# Sheet2.net
KiCad netlist of a schematic drawn in Altium Designer
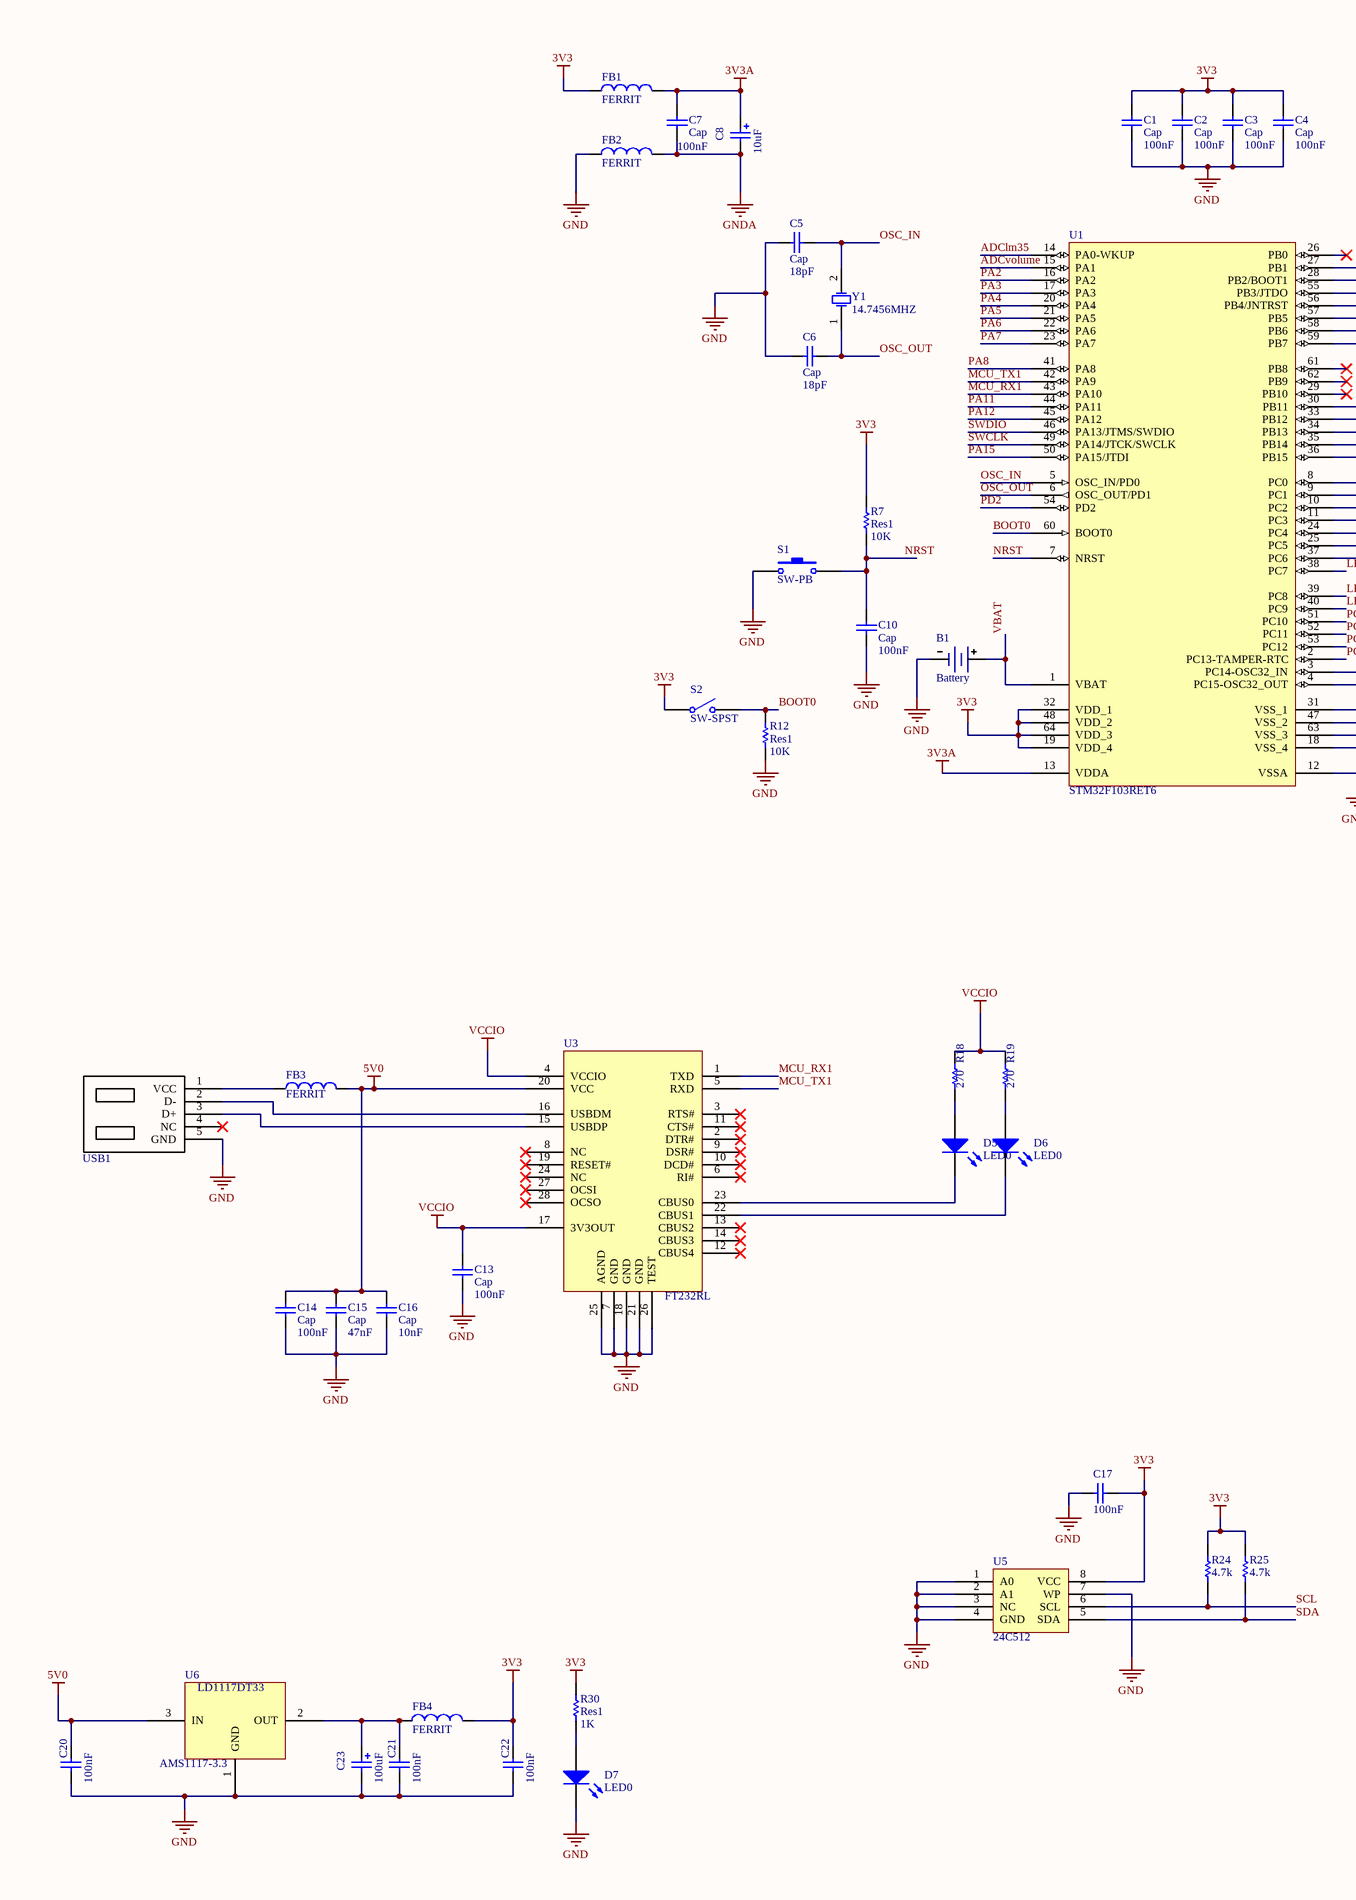
[diagram p0: Sheet2.SchDoc, left]
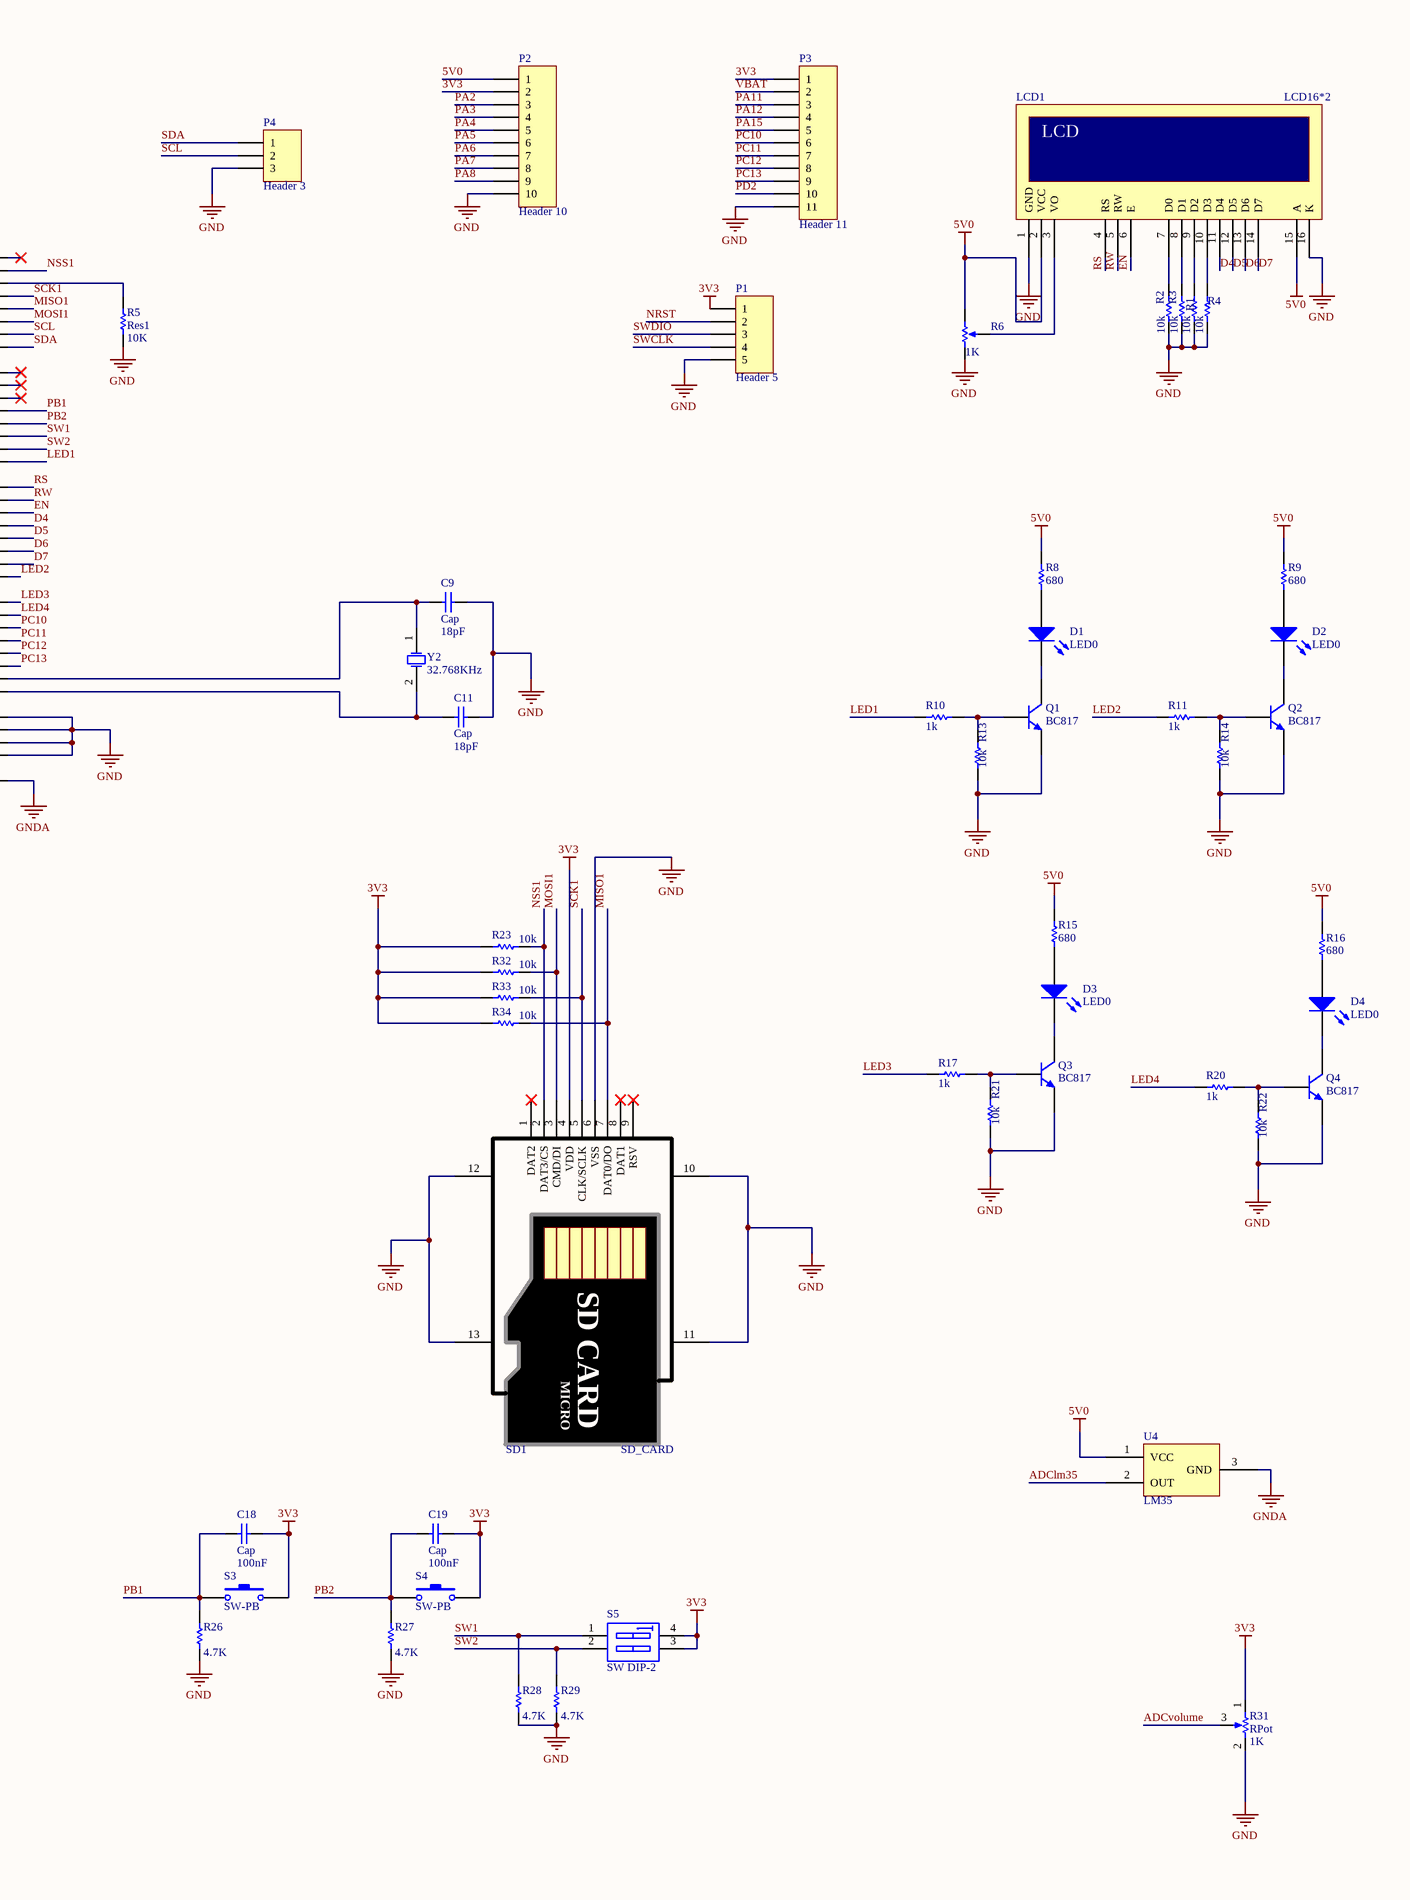
[diagram p1: Sheet2.SchDoc, right]

(export (version "E")
  (design (tool "Eeschema 10.0.6"))
  (components
    (comp (ref "B1")
      (value "Battery")
      (footprint "Battery socket SMD")
      (libsource (lib "ZetaBoard_Lib") (part "Battry Backup"))
    )
    (comp (ref "C1")
      (value "Cap")
      (footprint "SMD_805")
      (description "Capacitor")
      (fields (field (name "ALTIUM_VALUE") "100nF"))
      (libsource (lib "Miscellaneous Devices") (part "Cap"))
    )
    (comp (ref "C2")
      (value "Cap")
      (footprint "SMD_805")
      (description "Capacitor")
      (fields (field (name "ALTIUM_VALUE") "100nF"))
      (libsource (lib "Miscellaneous Devices") (part "Cap"))
    )
    (comp (ref "C3")
      (value "Cap")
      (footprint "SMD_805")
      (description "Capacitor")
      (fields (field (name "ALTIUM_VALUE") "100nF"))
      (libsource (lib "Miscellaneous Devices") (part "Cap"))
    )
    (comp (ref "C4")
      (value "Cap")
      (footprint "SMD_805")
      (description "Capacitor")
      (fields (field (name "ALTIUM_VALUE") "100nF"))
      (libsource (lib "Miscellaneous Devices") (part "Cap"))
    )
    (comp (ref "C5")
      (value "Cap")
      (footprint "SMD_805")
      (description "Capacitor")
      (fields (field (name "ALTIUM_VALUE") "18pF"))
      (libsource (lib "Miscellaneous Devices") (part "Cap"))
    )
    (comp (ref "C6")
      (value "Cap")
      (footprint "SMD_805")
      (description "Capacitor")
      (fields (field (name "ALTIUM_VALUE") "18pF"))
      (libsource (lib "Miscellaneous Devices") (part "Cap"))
    )
    (comp (ref "C7")
      (value "Cap")
      (footprint "SMD_805")
      (description "Capacitor")
      (fields (field (name "ALTIUM_VALUE") "100nF"))
      (libsource (lib "Miscellaneous Devices") (part "Cap"))
    )
    (comp (ref "C8")
      (value "10uF")
      (footprint "C_B")
      (description "Polarized Capacitor (Axial)")
      (fields (field (name "Comment") "Cap Pol2"))
      (libsource (lib "Miscellaneous Devices") (part "Cap Pol2"))
    )
    (comp (ref "C9")
      (value "Cap")
      (footprint "SMD_805")
      (description "Capacitor")
      (fields (field (name "ALTIUM_VALUE") "18pF"))
      (libsource (lib "Miscellaneous Devices") (part "Cap"))
    )
    (comp (ref "C10")
      (value "Cap")
      (footprint "SMD_805")
      (description "Capacitor")
      (fields (field (name "ALTIUM_VALUE") "100nF"))
      (libsource (lib "Miscellaneous Devices") (part "Cap"))
    )
    (comp (ref "C11")
      (value "Cap")
      (footprint "SMD_805")
      (description "Capacitor")
      (fields (field (name "ALTIUM_VALUE") "18pF"))
      (libsource (lib "Miscellaneous Devices") (part "Cap"))
    )
    (comp (ref "C13")
      (value "Cap")
      (footprint "SMD_805")
      (description "Capacitor")
      (fields (field (name "ALTIUM_VALUE") "100nF"))
      (libsource (lib "Miscellaneous Devices") (part "Cap"))
    )
    (comp (ref "C14")
      (value "Cap")
      (footprint "SMD_805")
      (description "Capacitor")
      (fields (field (name "ALTIUM_VALUE") "100nF"))
      (libsource (lib "Miscellaneous Devices") (part "Cap"))
    )
    (comp (ref "C15")
      (value "Cap")
      (footprint "SMD_805")
      (description "Capacitor")
      (fields (field (name "ALTIUM_VALUE") "47nF"))
      (libsource (lib "Miscellaneous Devices") (part "Cap"))
    )
    (comp (ref "C16")
      (value "Cap")
      (footprint "SMD_805")
      (description "Capacitor")
      (fields (field (name "ALTIUM_VALUE") "10nF"))
      (libsource (lib "Miscellaneous Devices") (part "Cap"))
    )
    (comp (ref "C17")
      (value "100nF")
      (footprint "SMD_805")
      (description "Capacitor")
      (fields (field (name "Comment") "Cap"))
      (libsource (lib "Miscellaneous Devices") (part "Cap"))
    )
    (comp (ref "C18")
      (value "Cap")
      (footprint "SMD_805")
      (description "Capacitor")
      (fields (field (name "ALTIUM_VALUE") "100nF"))
      (libsource (lib "Miscellaneous Devices") (part "Cap"))
    )
    (comp (ref "C19")
      (value "Cap")
      (footprint "SMD_805")
      (description "Capacitor")
      (fields (field (name "ALTIUM_VALUE") "100nF"))
      (libsource (lib "Miscellaneous Devices") (part "Cap"))
    )
    (comp (ref "C20")
      (value "100nF")
      (footprint "SMD_805")
      (description "Capacitor")
      (fields (field (name "Comment") "Cap"))
      (libsource (lib "Miscellaneous Devices") (part "Cap"))
    )
    (comp (ref "C21")
      (value "100nF")
      (footprint "SMD_805")
      (description "Capacitor")
      (fields (field (name "Comment") "Cap"))
      (libsource (lib "Miscellaneous Devices") (part "Cap"))
    )
    (comp (ref "C22")
      (value "100nF")
      (footprint "SMD_805")
      (description "Capacitor")
      (fields (field (name "Comment") "Cap"))
      (libsource (lib "Miscellaneous Devices") (part "Cap"))
    )
    (comp (ref "C23")
      (value "100uF")
      (footprint "C_B")
      (description "Polarized Capacitor (Axial)")
      (fields (field (name "Comment") "Cap Pol2"))
      (libsource (lib "Miscellaneous Devices") (part "Cap Pol2"))
    )
    (comp (ref "D1")
      (value "LED0")
      (footprint "SMD_805")
      (description "Typical INFRARED GaAs LED")
      (libsource (lib "Miscellaneous Devices") (part "LED0"))
    )
    (comp (ref "D2")
      (value "LED0")
      (footprint "SMD_805")
      (description "Typical INFRARED GaAs LED")
      (libsource (lib "Miscellaneous Devices") (part "LED0"))
    )
    (comp (ref "D3")
      (value "LED0")
      (footprint "SMD_805")
      (description "Typical INFRARED GaAs LED")
      (libsource (lib "Miscellaneous Devices") (part "LED0"))
    )
    (comp (ref "D4")
      (value "LED0")
      (footprint "SMD_805")
      (description "Typical INFRARED GaAs LED")
      (libsource (lib "Miscellaneous Devices") (part "LED0"))
    )
    (comp (ref "D5")
      (value "LED0")
      (footprint "SMD_805")
      (description "Typical INFRARED GaAs LED")
      (libsource (lib "Miscellaneous Devices") (part "LED0"))
    )
    (comp (ref "D6")
      (value "LED0")
      (footprint "SMD_805")
      (description "Typical INFRARED GaAs LED")
      (libsource (lib "Miscellaneous Devices") (part "LED0"))
    )
    (comp (ref "D7")
      (value "LED0")
      (footprint "SMD_805")
      (description "Typical INFRARED GaAs LED")
      (libsource (lib "Miscellaneous Devices") (part "LED0"))
    )
    (comp (ref "FB1")
      (value "FERRIT")
      (footprint "SMD_805")
      (description "Inductor")
      (libsource (lib "Miscellaneous Devices") (part "Inductor"))
    )
    (comp (ref "FB2")
      (value "FERRIT")
      (footprint "SMD_805")
      (description "Inductor")
      (libsource (lib "Miscellaneous Devices") (part "Inductor"))
    )
    (comp (ref "FB3")
      (value "FERRIT")
      (footprint "SMD_805")
      (description "Inductor")
      (libsource (lib "Miscellaneous Devices") (part "Inductor"))
    )
    (comp (ref "FB4")
      (value "FERRIT")
      (footprint "SMD_805")
      (description "Inductor")
      (libsource (lib "Miscellaneous Devices") (part "Inductor"))
    )
    (comp (ref "LCD1") (value "LCD16*2") (footprint "LCD2X16") (libsource (lib "LCD") (part "LCD16*2")))
    (comp (ref "P1")
      (value "Header 5")
      (footprint "HDR1X5")
      (description "Header, 5-Pin")
      (libsource (lib "Miscellaneous Connectors") (part "Header 5"))
    )
    (comp (ref "P2")
      (value "Header 10")
      (footprint "HDR1X10")
      (description "Header, 10-Pin")
      (libsource (lib "Miscellaneous Connectors") (part "Header 10"))
    )
    (comp (ref "P3")
      (value "Header 11")
      (footprint "HDR1X11")
      (description "Header, 11-Pin")
      (libsource (lib "Miscellaneous Connectors") (part "Header 11"))
    )
    (comp (ref "P4")
      (value "Header 3")
      (footprint "HDR1X3")
      (description "Header, 3-Pin")
      (libsource (lib "Miscellaneous Connectors") (part "Header 3"))
    )
    (comp (ref "Q1")
      (value "BC817")
      (footprint "SOT23")
      (description "NPN General Purpose Amplifier")
      (libsource (lib "Miscellaneous Devices") (part "2N3904"))
    )
    (comp (ref "Q2")
      (value "BC817")
      (footprint "SOT23")
      (description "NPN General Purpose Amplifier")
      (libsource (lib "Miscellaneous Devices") (part "2N3904"))
    )
    (comp (ref "Q3")
      (value "BC817")
      (footprint "SOT23")
      (description "NPN General Purpose Amplifier")
      (libsource (lib "Miscellaneous Devices") (part "2N3904"))
    )
    (comp (ref "Q4")
      (value "BC817")
      (footprint "SOT23")
      (description "NPN General Purpose Amplifier")
      (libsource (lib "Miscellaneous Devices") (part "2N3904"))
    )
    (comp (ref "R1")
      (value "10k")
      (footprint "SMD_805")
      (description "Resistor")
      (fields (field (name "Comment") "Res1"))
      (libsource (lib "Miscellaneous Devices") (part "Res1"))
    )
    (comp (ref "R2")
      (value "10k")
      (footprint "SMD_805")
      (description "Resistor")
      (fields (field (name "Comment") "Res1"))
      (libsource (lib "Miscellaneous Devices") (part "Res1"))
    )
    (comp (ref "R3")
      (value "10k")
      (footprint "SMD_805")
      (description "Resistor")
      (fields (field (name "Comment") "Res1"))
      (libsource (lib "Miscellaneous Devices") (part "Res1"))
    )
    (comp (ref "R4")
      (value "10k")
      (footprint "SMD_805")
      (description "Resistor")
      (fields (field (name "Comment") "Res1"))
      (libsource (lib "Miscellaneous Devices") (part "Res1"))
    )
    (comp (ref "R5")
      (value "Res1")
      (footprint "SMD_805")
      (description "Resistor")
      (fields (field (name "ALTIUM_VALUE") "10K"))
      (libsource (lib "Miscellaneous Devices") (part "Res1"))
    )
    (comp (ref "R6")
      (value "1K")
      (footprint "pot")
      (description "Potentiometer")
      (fields (field (name "Comment") "RPot"))
      (libsource (lib "Miscellaneous Devices") (part "RPot"))
    )
    (comp (ref "R7")
      (value "Res1")
      (footprint "SMD_805")
      (description "Resistor")
      (fields (field (name "ALTIUM_VALUE") "10K"))
      (libsource (lib "Miscellaneous Devices") (part "Res1"))
    )
    (comp (ref "R8")
      (value "680")
      (footprint "SMD_805")
      (description "Resistor")
      (fields (field (name "Comment") "Res1"))
      (libsource (lib "Miscellaneous Devices") (part "Res1"))
    )
    (comp (ref "R9")
      (value "680")
      (footprint "SMD_805")
      (description "Resistor")
      (fields (field (name "Comment") "Res1"))
      (libsource (lib "Miscellaneous Devices") (part "Res1"))
    )
    (comp (ref "R10")
      (value "1k")
      (footprint "SMD_805")
      (description "Resistor")
      (fields (field (name "Comment") "Res1"))
      (libsource (lib "Miscellaneous Devices") (part "Res1"))
    )
    (comp (ref "R11")
      (value "1k")
      (footprint "SMD_805")
      (description "Resistor")
      (fields (field (name "Comment") "Res1"))
      (libsource (lib "Miscellaneous Devices") (part "Res1"))
    )
    (comp (ref "R12")
      (value "Res1")
      (footprint "SMD_805")
      (description "Resistor")
      (fields (field (name "ALTIUM_VALUE") "10K"))
      (libsource (lib "Miscellaneous Devices") (part "Res1"))
    )
    (comp (ref "R13")
      (value "10k")
      (footprint "SMD_805")
      (description "Resistor")
      (fields (field (name "Comment") "Res1"))
      (libsource (lib "Miscellaneous Devices") (part "Res1"))
    )
    (comp (ref "R14")
      (value "10k")
      (footprint "SMD_805")
      (description "Resistor")
      (fields (field (name "Comment") "Res1"))
      (libsource (lib "Miscellaneous Devices") (part "Res1"))
    )
    (comp (ref "R15")
      (value "680")
      (footprint "SMD_805")
      (description "Resistor")
      (fields (field (name "Comment") "Res1"))
      (libsource (lib "Miscellaneous Devices") (part "Res1"))
    )
    (comp (ref "R16")
      (value "680")
      (footprint "SMD_805")
      (description "Resistor")
      (fields (field (name "Comment") "Res1"))
      (libsource (lib "Miscellaneous Devices") (part "Res1"))
    )
    (comp (ref "R17")
      (value "1k")
      (footprint "SMD_805")
      (description "Resistor")
      (fields (field (name "Comment") "Res1"))
      (libsource (lib "Miscellaneous Devices") (part "Res1"))
    )
    (comp (ref "R18")
      (value "270")
      (footprint "SMD_805")
      (description "Resistor")
      (fields (field (name "Comment") "Res1"))
      (libsource (lib "Miscellaneous Devices") (part "Res1"))
    )
    (comp (ref "R19")
      (value "270")
      (footprint "SMD_805")
      (description "Resistor")
      (fields (field (name "Comment") "Res1"))
      (libsource (lib "Miscellaneous Devices") (part "Res1"))
    )
    (comp (ref "R20")
      (value "1k")
      (footprint "SMD_805")
      (description "Resistor")
      (fields (field (name "Comment") "Res1"))
      (libsource (lib "Miscellaneous Devices") (part "Res1"))
    )
    (comp (ref "R21")
      (value "10k")
      (footprint "SMD_805")
      (description "Resistor")
      (fields (field (name "Comment") "Res1"))
      (libsource (lib "Miscellaneous Devices") (part "Res1"))
    )
    (comp (ref "R22")
      (value "10k")
      (footprint "SMD_805")
      (description "Resistor")
      (fields (field (name "Comment") "Res1"))
      (libsource (lib "Miscellaneous Devices") (part "Res1"))
    )
    (comp (ref "R23")
      (value "10k")
      (footprint "SMD_805")
      (description "Resistor")
      (fields (field (name "Comment") "Res1"))
      (libsource (lib "Miscellaneous Devices") (part "Res1"))
    )
    (comp (ref "R24")
      (value "4.7k")
      (footprint "SMD_805")
      (description "Resistor")
      (fields (field (name "Comment") "Res1"))
      (libsource (lib "Miscellaneous Devices") (part "Res1"))
    )
    (comp (ref "R25")
      (value "4.7k")
      (footprint "SMD_805")
      (description "Resistor")
      (fields (field (name "Comment") "Res1"))
      (libsource (lib "Miscellaneous Devices") (part "Res1"))
    )
    (comp (ref "R26")
      (value "4.7K")
      (footprint "SMD_805")
      (description "Resistor")
      (fields (field (name "Comment") "Res1"))
      (libsource (lib "Miscellaneous Devices") (part "Res1"))
    )
    (comp (ref "R27")
      (value "4.7K")
      (footprint "SMD_805")
      (description "Resistor")
      (fields (field (name "Comment") "Res1"))
      (libsource (lib "Miscellaneous Devices") (part "Res1"))
    )
    (comp (ref "R28")
      (value "4.7K")
      (footprint "SMD_805")
      (description "Resistor")
      (fields (field (name "Comment") "Res1"))
      (libsource (lib "Miscellaneous Devices") (part "Res1"))
    )
    (comp (ref "R29")
      (value "4.7K")
      (footprint "SMD_805")
      (description "Resistor")
      (fields (field (name "Comment") "Res1"))
      (libsource (lib "Miscellaneous Devices") (part "Res1"))
    )
    (comp (ref "R30")
      (value "Res1")
      (footprint "SMD_805")
      (description "Resistor")
      (fields (field (name "ALTIUM_VALUE") "1K"))
      (libsource (lib "Miscellaneous Devices") (part "Res1"))
    )
    (comp (ref "R31")
      (value "RPot")
      (footprint "pot")
      (description "Potentiometer")
      (fields (field (name "ALTIUM_VALUE") "1K"))
      (libsource (lib "") (part "RPot_1"))
    )
    (comp (ref "R32")
      (value "10k")
      (footprint "SMD_805")
      (description "Resistor")
      (fields (field (name "Comment") "Res1"))
      (libsource (lib "Miscellaneous Devices") (part "Res1"))
    )
    (comp (ref "R33")
      (value "10k")
      (footprint "SMD_805")
      (description "Resistor")
      (fields (field (name "Comment") "Res1"))
      (libsource (lib "Miscellaneous Devices") (part "Res1"))
    )
    (comp (ref "R34")
      (value "10k")
      (footprint "SMD_805")
      (description "Resistor")
      (fields (field (name "Comment") "Res1"))
      (libsource (lib "Miscellaneous Devices") (part "Res1"))
    )
    (comp (ref "S1")
      (value "SW-PB")
      (footprint "smd_button")
      (description "Switch")
      (libsource (lib "Miscellaneous Devices") (part "SW-PB"))
    )
    (comp (ref "S2")
      (value "SW-SPST")
      (footprint "KEY1")
      (description "Single-Pole, Single-Throw Switch")
      (libsource (lib "Miscellaneous Devices") (part "SW-SPST"))
    )
    (comp (ref "S3")
      (value "SW-PB")
      (footprint "smd_button")
      (description "Switch")
      (libsource (lib "Miscellaneous Devices") (part "SW-PB"))
    )
    (comp (ref "S4")
      (value "SW-PB")
      (footprint "smd_button")
      (description "Switch")
      (libsource (lib "Miscellaneous Devices") (part "SW-PB"))
    )
    (comp (ref "S5")
      (value "SW DIP-2")
      (footprint "DIP-4")
      (description "DIP Switch, 2 Position, SPST")
      (libsource (lib "Miscellaneous Devices") (part "SW DIP-2"))
    )
    (comp (ref "SD1")
      (value "SD_CARD")
      (footprint "Micro SD Card")
      (libsource (lib "MICRO_SD_CARD_HOLDER") (part "MICRO_SD_CARD_HOLDER"))
    )
    (comp (ref "U1")
      (value "STM32F103RET6")
      (footprint "LQFP64")
      (description "STM32 ARM-based 32-bit MCU with 64 Kbytes Flash, 64-pin LQFP, Industrial Temperature")
      (libsource (lib "ST Microcontroller 32-Bit STM32") (part "STM32F103R8T6"))
    )
    (comp (ref "U3") (value "FT232RL") (footprint "SOP28") (libsource (lib "FT232RL") (part "FT232RL")))
    (comp (ref "U4")
      (value "LM35")
      (footprint "LM35-TO92")
      (description "LM35 Temperature Sensor")
      (libsource (lib "altium-import") (part "root_0_LM35_"))
    )
    (comp (ref "U5") (value "24C512") (footprint "SOP8") (libsource (lib "24Cxx") (part "24Cxx")))
    (comp (ref "U6")
      (value "AMS1117-3.3")
      (footprint "SOT223")
      (libsource (lib "LD1117DT33") (part "LD1117DT33"))
    )
    (comp (ref "USB1")
      (value "MICRO_USB")
      (footprint "MINI_USB")
      (libsource (lib "MICRO_USB") (part "MICRO_USB"))
    )
    (comp (ref "Y1")
      (value "14.7456MHZ")
      (footprint "xtal_smd")
      (description "Crystal Oscillator")
      (libsource (lib "Miscellaneous Devices") (part "XTAL"))
    )
    (comp (ref "Y2")
      (value "32.768KHz")
      (footprint "XTAL_RTC")
      (description "Crystal Oscillator")
      (libsource (lib "Miscellaneous Devices") (part "XTAL"))
    )
  )
  (nets
    (net (code "1") (name "/ADClm35") (class "Default")
      (node (ref "U1") (pin "14") (pinfunction "PA0-WKUP_14") (pintype "bidirectional"))
      (node (ref "U4") (pin "2") (pinfunction "OUT_2") (pintype "passive"))
    )
    (net (code "2") (name "/ADCvolume") (class "Default")
      (node (ref "R31") (pin "3") (pinfunction "TAP_3") (pintype "passive"))
      (node (ref "U1") (pin "15") (pinfunction "PA1_15") (pintype "bidirectional"))
    )
    (net (code "3") (name "/BOOT0") (class "Default")
      (node (ref "R12") (pin "2") (pinfunction "2_2") (pintype "passive"))
      (node (ref "S2") (pin "2") (pinfunction "NO_2") (pintype "passive"))
      (node (ref "U1") (pin "60") (pinfunction "BOOT0_60") (pintype "input"))
    )
    (net (code "4") (name "/D4") (class "Default")
      (node (ref "LCD1") (pin "11") (pinfunction "D4_11") (pintype "passive"))
      (node (ref "U1") (pin "11") (pinfunction "PC3_11") (pintype "bidirectional"))
    )
    (net (code "5") (name "/D5") (class "Default")
      (node (ref "LCD1") (pin "12") (pinfunction "D5_12") (pintype "passive"))
      (node (ref "U1") (pin "24") (pinfunction "PC4_24") (pintype "bidirectional"))
    )
    (net (code "6") (name "/D6") (class "Default")
      (node (ref "LCD1") (pin "13") (pinfunction "D6_13") (pintype "passive"))
      (node (ref "U1") (pin "25") (pinfunction "PC5_25") (pintype "bidirectional"))
    )
    (net (code "7") (name "/D7") (class "Default")
      (node (ref "LCD1") (pin "14") (pinfunction "D7_14") (pintype "passive"))
      (node (ref "U1") (pin "37") (pinfunction "PC6_37") (pintype "bidirectional"))
    )
    (net (code "8") (name "/EN") (class "Default")
      (node (ref "LCD1") (pin "6") (pinfunction "E_6") (pintype "passive"))
      (node (ref "U1") (pin "10") (pinfunction "PC2_10") (pintype "bidirectional"))
    )
    (net (code "9") (name "/LED1") (class "Default")
      (node (ref "R10") (pin "1") (pinfunction "1_1") (pintype "passive"))
      (node (ref "U1") (pin "36") (pinfunction "PB15_36") (pintype "bidirectional"))
    )
    (net (code "10") (name "/LED2") (class "Default")
      (node (ref "R11") (pin "1") (pinfunction "1_1") (pintype "passive"))
      (node (ref "U1") (pin "38") (pinfunction "PC7_38") (pintype "bidirectional"))
    )
    (net (code "11") (name "/LED3") (class "Default")
      (node (ref "R17") (pin "1") (pinfunction "1_1") (pintype "passive"))
      (node (ref "U1") (pin "39") (pinfunction "PC8_39") (pintype "bidirectional"))
    )
    (net (code "12") (name "/LED4") (class "Default")
      (node (ref "R20") (pin "1") (pinfunction "1_1") (pintype "passive"))
      (node (ref "U1") (pin "40") (pinfunction "PC9_40") (pintype "bidirectional"))
    )
    (net (code "13") (name "/MCU_RX1") (class "Default")
      (node (ref "U1") (pin "43") (pinfunction "PA10_43") (pintype "bidirectional"))
      (node (ref "U3") (pin "1") (pinfunction "TXD_1") (pintype "passive"))
    )
    (net (code "14") (name "/MCU_TX1") (class "Default")
      (node (ref "U1") (pin "42") (pinfunction "PA9_42") (pintype "bidirectional"))
      (node (ref "U3") (pin "5") (pinfunction "RXD_5") (pintype "passive"))
    )
    (net (code "15") (name "/MISO1") (class "Default")
      (node (ref "R34") (pin "1") (pinfunction "1_1") (pintype "passive"))
      (node (ref "SD1") (pin "7") (pinfunction "DAT0/DO_7") (pintype "passive"))
      (node (ref "U1") (pin "56") (pinfunction "PB4/JNTRST_56") (pintype "bidirectional"))
    )
    (net (code "16") (name "/MOSI1") (class "Default")
      (node (ref "R32") (pin "1") (pinfunction "1_1") (pintype "passive"))
      (node (ref "SD1") (pin "3") (pinfunction "CMD/DI_3") (pintype "passive"))
      (node (ref "U1") (pin "57") (pinfunction "PB5_57") (pintype "bidirectional"))
    )
    (net (code "17") (name "/NRST") (class "Default")
      (node (ref "C10") (pin "2") (pinfunction "2_2") (pintype "passive"))
      (node (ref "P1") (pin "2") (pinfunction "2_2") (pintype "passive"))
      (node (ref "R7") (pin "1") (pinfunction "1_1") (pintype "passive"))
      (node (ref "S1") (pin "2") (pinfunction "2_2") (pintype "passive"))
      (node (ref "U1") (pin "7") (pinfunction "NRST_7") (pintype "bidirectional"))
    )
    (net (code "18") (name "/NSS1") (class "Default")
      (node (ref "R23") (pin "1") (pinfunction "1_1") (pintype "passive"))
      (node (ref "SD1") (pin "2") (pinfunction "DAT3/CS_2") (pintype "passive"))
      (node (ref "U1") (pin "27") (pinfunction "PB1_27") (pintype "bidirectional"))
    )
    (net (code "19") (name "/OSC_IN") (class "Default")
      (node (ref "C5") (pin "2") (pinfunction "2_2") (pintype "passive"))
      (node (ref "U1") (pin "5") (pinfunction "OSC_IN/PD0_5") (pintype "input"))
      (node (ref "Y1") (pin "2") (pinfunction "OSC2_2") (pintype "passive"))
    )
    (net (code "20") (name "/OSC_OUT") (class "Default")
      (node (ref "C6") (pin "2") (pinfunction "2_2") (pintype "passive"))
      (node (ref "U1") (pin "6") (pinfunction "OSC_OUT/PD1_6") (pintype "output"))
      (node (ref "Y1") (pin "1") (pinfunction "OSC1_1") (pintype "passive"))
    )
    (net (code "21") (name "/PA2") (class "Default")
      (node (ref "P2") (pin "3") (pinfunction "3_3") (pintype "passive"))
      (node (ref "U1") (pin "16") (pinfunction "PA2_16") (pintype "bidirectional"))
    )
    (net (code "22") (name "/PA3") (class "Default")
      (node (ref "P2") (pin "4") (pinfunction "4_4") (pintype "passive"))
      (node (ref "U1") (pin "17") (pinfunction "PA3_17") (pintype "bidirectional"))
    )
    (net (code "23") (name "/PA4") (class "Default")
      (node (ref "P2") (pin "5") (pinfunction "5_5") (pintype "passive"))
      (node (ref "U1") (pin "20") (pinfunction "PA4_20") (pintype "bidirectional"))
    )
    (net (code "24") (name "/PA5") (class "Default")
      (node (ref "P2") (pin "6") (pinfunction "6_6") (pintype "passive"))
      (node (ref "U1") (pin "21") (pinfunction "PA5_21") (pintype "bidirectional"))
    )
    (net (code "25") (name "/PA6") (class "Default")
      (node (ref "P2") (pin "7") (pinfunction "7_7") (pintype "passive"))
      (node (ref "U1") (pin "22") (pinfunction "PA6_22") (pintype "bidirectional"))
    )
    (net (code "26") (name "/PA7") (class "Default")
      (node (ref "P2") (pin "8") (pinfunction "8_8") (pintype "passive"))
      (node (ref "U1") (pin "23") (pinfunction "PA7_23") (pintype "bidirectional"))
    )
    (net (code "27") (name "/PA8") (class "Default")
      (node (ref "P2") (pin "9") (pinfunction "9_9") (pintype "passive"))
      (node (ref "U1") (pin "41") (pinfunction "PA8_41") (pintype "bidirectional"))
    )
    (net (code "28") (name "/PA11") (class "Default")
      (node (ref "P3") (pin "3") (pinfunction "3_3") (pintype "passive"))
      (node (ref "U1") (pin "44") (pinfunction "PA11_44") (pintype "bidirectional"))
    )
    (net (code "29") (name "/PA12") (class "Default")
      (node (ref "P3") (pin "4") (pinfunction "4_4") (pintype "passive"))
      (node (ref "U1") (pin "45") (pinfunction "PA12_45") (pintype "bidirectional"))
    )
    (net (code "30") (name "/PA15") (class "Default")
      (node (ref "P3") (pin "5") (pinfunction "5_5") (pintype "passive"))
      (node (ref "U1") (pin "50") (pinfunction "PA15/JTDI_50") (pintype "bidirectional"))
    )
    (net (code "31") (name "/PB1") (class "Default")
      (node (ref "C18") (pin "1") (pinfunction "1_1") (pintype "passive"))
      (node (ref "R26") (pin "2") (pinfunction "2_2") (pintype "passive"))
      (node (ref "S3") (pin "1") (pinfunction "1_1") (pintype "passive"))
      (node (ref "U1") (pin "30") (pinfunction "PB11_30") (pintype "bidirectional"))
    )
    (net (code "32") (name "/PB2") (class "Default")
      (node (ref "C19") (pin "1") (pinfunction "1_1") (pintype "passive"))
      (node (ref "R27") (pin "2") (pinfunction "2_2") (pintype "passive"))
      (node (ref "S4") (pin "1") (pinfunction "1_1") (pintype "passive"))
      (node (ref "U1") (pin "33") (pinfunction "PB12_33") (pintype "bidirectional"))
    )
    (net (code "33") (name "/PC10") (class "Default")
      (node (ref "P3") (pin "6") (pinfunction "6_6") (pintype "passive"))
      (node (ref "U1") (pin "51") (pinfunction "PC10_51") (pintype "bidirectional"))
    )
    (net (code "34") (name "/PC11") (class "Default")
      (node (ref "P3") (pin "7") (pinfunction "7_7") (pintype "passive"))
      (node (ref "U1") (pin "52") (pinfunction "PC11_52") (pintype "bidirectional"))
    )
    (net (code "35") (name "/PC12") (class "Default")
      (node (ref "P3") (pin "8") (pinfunction "8_8") (pintype "passive"))
      (node (ref "U1") (pin "53") (pinfunction "PC12_53") (pintype "bidirectional"))
    )
    (net (code "36") (name "/PC13") (class "Default")
      (node (ref "P3") (pin "9") (pinfunction "9_9") (pintype "passive"))
      (node (ref "U1") (pin "2") (pinfunction "PC13-TAMPER-RTC_2") (pintype "bidirectional"))
    )
    (net (code "37") (name "/PD2") (class "Default")
      (node (ref "P3") (pin "10") (pinfunction "10_10") (pintype "passive"))
      (node (ref "U1") (pin "54") (pinfunction "PD2_54") (pintype "bidirectional"))
    )
    (net (code "38") (name "/RS") (class "Default")
      (node (ref "LCD1") (pin "4") (pinfunction "RS_4") (pintype "passive"))
      (node (ref "U1") (pin "8") (pinfunction "PC0_8") (pintype "bidirectional"))
    )
    (net (code "39") (name "/RW") (class "Default")
      (node (ref "LCD1") (pin "5") (pinfunction "RW_5") (pintype "passive"))
      (node (ref "U1") (pin "9") (pinfunction "PC1_9") (pintype "bidirectional"))
    )
    (net (code "40") (name "/SCK1") (class "Default")
      (node (ref "R33") (pin "1") (pinfunction "1_1") (pintype "passive"))
      (node (ref "SD1") (pin "5") (pinfunction "CLK/SCLK_5") (pintype "passive"))
      (node (ref "U1") (pin "55") (pinfunction "PB3/JTDO_55") (pintype "bidirectional"))
    )
    (net (code "41") (name "/SCL") (class "Default")
      (node (ref "P4") (pin "2") (pinfunction "2_2") (pintype "passive"))
      (node (ref "R24") (pin "1") (pinfunction "1_1") (pintype "passive"))
      (node (ref "U1") (pin "58") (pinfunction "PB6_58") (pintype "bidirectional"))
      (node (ref "U5") (pin "6") (pinfunction "SCL_6") (pintype "passive"))
    )
    (net (code "42") (name "/SDA") (class "Default")
      (node (ref "P4") (pin "1") (pinfunction "1_1") (pintype "passive"))
      (node (ref "R25") (pin "1") (pinfunction "1_1") (pintype "passive"))
      (node (ref "U1") (pin "59") (pinfunction "PB7_59") (pintype "bidirectional"))
      (node (ref "U5") (pin "5") (pinfunction "SDA_5") (pintype "passive"))
    )
    (net (code "43") (name "/SW1") (class "Default")
      (node (ref "R28") (pin "2") (pinfunction "2_2") (pintype "passive"))
      (node (ref "S5") (pin "1") (pinfunction "A1_1") (pintype "passive"))
      (node (ref "U1") (pin "34") (pinfunction "PB13_34") (pintype "bidirectional"))
    )
    (net (code "44") (name "/SW2") (class "Default")
      (node (ref "R29") (pin "2") (pinfunction "2_2") (pintype "passive"))
      (node (ref "S5") (pin "2") (pinfunction "A2_2") (pintype "passive"))
      (node (ref "U1") (pin "35") (pinfunction "PB14_35") (pintype "bidirectional"))
    )
    (net (code "45") (name "/SWCLK") (class "Default")
      (node (ref "P1") (pin "4") (pinfunction "4_4") (pintype "passive"))
      (node (ref "U1") (pin "49") (pinfunction "PA14/JTCK/SWCLK_49") (pintype "bidirectional"))
    )
    (net (code "46") (name "/SWDIO") (class "Default")
      (node (ref "P1") (pin "3") (pinfunction "3_3") (pintype "passive"))
      (node (ref "U1") (pin "46") (pinfunction "PA13/JTMS/SWDIO_46") (pintype "bidirectional"))
    )
    (net (code "47") (name "/VBAT") (class "Default")
      (node (ref "B1") (pin "1") (pinfunction "+_1") (pintype "passive"))
      (node (ref "P3") (pin "2") (pinfunction "2_2") (pintype "passive"))
      (node (ref "U1") (pin "1") (pinfunction "VBAT_1") (pintype "power_in"))
    )
    (net (code "48") (name "3V3") (class "Default")
      (node (ref "C1") (pin "2") (pinfunction "2_2") (pintype "passive"))
      (node (ref "C17") (pin "2") (pinfunction "2_2") (pintype "passive"))
      (node (ref "C18") (pin "2") (pinfunction "2_2") (pintype "passive"))
      (node (ref "C19") (pin "2") (pinfunction "2_2") (pintype "passive"))
      (node (ref "C2") (pin "2") (pinfunction "2_2") (pintype "passive"))
      (node (ref "C22") (pin "2") (pinfunction "2_2") (pintype "passive"))
      (node (ref "C3") (pin "2") (pinfunction "2_2") (pintype "passive"))
      (node (ref "C4") (pin "2") (pinfunction "2_2") (pintype "passive"))
      (node (ref "FB1") (pin "1") (pinfunction "1_1") (pintype "passive"))
      (node (ref "FB4") (pin "2") (pinfunction "2_2") (pintype "passive"))
      (node (ref "P1") (pin "1") (pinfunction "1_1") (pintype "passive"))
      (node (ref "P2") (pin "2") (pinfunction "2_2") (pintype "passive"))
      (node (ref "P3") (pin "1") (pinfunction "1_1") (pintype "passive"))
      (node (ref "R23") (pin "2") (pinfunction "2_2") (pintype "passive"))
      (node (ref "R24") (pin "2") (pinfunction "2_2") (pintype "passive"))
      (node (ref "R25") (pin "2") (pinfunction "2_2") (pintype "passive"))
      (node (ref "R30") (pin "2") (pinfunction "2_2") (pintype "passive"))
      (node (ref "R31") (pin "1") (pinfunction "TOP_1") (pintype "passive"))
      (node (ref "R32") (pin "2") (pinfunction "2_2") (pintype "passive"))
      (node (ref "R33") (pin "2") (pinfunction "2_2") (pintype "passive"))
      (node (ref "R34") (pin "2") (pinfunction "2_2") (pintype "passive"))
      (node (ref "R7") (pin "2") (pinfunction "2_2") (pintype "passive"))
      (node (ref "S2") (pin "1") (pinfunction "COMMON_1") (pintype "passive"))
      (node (ref "S3") (pin "2") (pinfunction "2_2") (pintype "passive"))
      (node (ref "S4") (pin "2") (pinfunction "2_2") (pintype "passive"))
      (node (ref "S5") (pin "3") (pinfunction "B2_3") (pintype "passive"))
      (node (ref "S5") (pin "4") (pinfunction "B1_4") (pintype "passive"))
      (node (ref "SD1") (pin "4") (pinfunction "VDD_4") (pintype "passive"))
      (node (ref "U1") (pin "19") (pinfunction "VDD_4_19") (pintype "power_in"))
      (node (ref "U1") (pin "32") (pinfunction "VDD_1_32") (pintype "power_in"))
      (node (ref "U1") (pin "48") (pinfunction "VDD_2_48") (pintype "power_in"))
      (node (ref "U1") (pin "64") (pinfunction "VDD_3_64") (pintype "power_in"))
      (node (ref "U5") (pin "8") (pinfunction "VCC_8") (pintype "passive"))
    )
    (net (code "49") (name "3V3A") (class "Default")
      (node (ref "C7") (pin "2") (pinfunction "2_2") (pintype "passive"))
      (node (ref "C8") (pin "1") (pinfunction "1_1") (pintype "passive"))
      (node (ref "FB1") (pin "2") (pinfunction "2_2") (pintype "passive"))
      (node (ref "U1") (pin "13") (pinfunction "VDDA_13") (pintype "power_in"))
    )
    (net (code "50") (name "5V0") (class "Default")
      (node (ref "C14") (pin "2") (pinfunction "2_2") (pintype "passive"))
      (node (ref "C15") (pin "2") (pinfunction "2_2") (pintype "passive"))
      (node (ref "C16") (pin "2") (pinfunction "2_2") (pintype "passive"))
      (node (ref "C20") (pin "2") (pinfunction "2_2") (pintype "passive"))
      (node (ref "FB3") (pin "2") (pinfunction "2_2") (pintype "passive"))
      (node (ref "LCD1") (pin "15") (pinfunction "A_15") (pintype "passive"))
      (node (ref "LCD1") (pin "2") (pinfunction "VCC_2") (pintype "passive"))
      (node (ref "P2") (pin "1") (pinfunction "1_1") (pintype "passive"))
      (node (ref "R15") (pin "2") (pinfunction "2_2") (pintype "passive"))
      (node (ref "R16") (pin "2") (pinfunction "2_2") (pintype "passive"))
      (node (ref "R6") (pin "2") (pinfunction "BOT_2") (pintype "passive"))
      (node (ref "R8") (pin "2") (pinfunction "2_2") (pintype "passive"))
      (node (ref "R9") (pin "2") (pinfunction "2_2") (pintype "passive"))
      (node (ref "U3") (pin "20") (pinfunction "VCC_20") (pintype "passive"))
      (node (ref "U4") (pin "1") (pinfunction "VCC_1") (pintype "passive"))
      (node (ref "U6") (pin "3") (pinfunction "IN_3") (pintype "passive"))
    )
    (net (code "51") (name "GND") (class "Default")
      (node (ref "B1") (pin "2") (pinfunction "-_2") (pintype "passive"))
      (node (ref "C1") (pin "1") (pinfunction "1_1") (pintype "passive"))
      (node (ref "C10") (pin "1") (pinfunction "1_1") (pintype "passive"))
      (node (ref "C11") (pin "1") (pinfunction "1_1") (pintype "passive"))
      (node (ref "C13") (pin "1") (pinfunction "1_1") (pintype "passive"))
      (node (ref "C14") (pin "1") (pinfunction "1_1") (pintype "passive"))
      (node (ref "C15") (pin "1") (pinfunction "1_1") (pintype "passive"))
      (node (ref "C16") (pin "1") (pinfunction "1_1") (pintype "passive"))
      (node (ref "C17") (pin "1") (pinfunction "1_1") (pintype "passive"))
      (node (ref "C2") (pin "1") (pinfunction "1_1") (pintype "passive"))
      (node (ref "C20") (pin "1") (pinfunction "1_1") (pintype "passive"))
      (node (ref "C21") (pin "1") (pinfunction "1_1") (pintype "passive"))
      (node (ref "C22") (pin "1") (pinfunction "1_1") (pintype "passive"))
      (node (ref "C23") (pin "2") (pinfunction "2_2") (pintype "passive"))
      (node (ref "C3") (pin "1") (pinfunction "1_1") (pintype "passive"))
      (node (ref "C4") (pin "1") (pinfunction "1_1") (pintype "passive"))
      (node (ref "C5") (pin "1") (pinfunction "1_1") (pintype "passive"))
      (node (ref "C6") (pin "1") (pinfunction "1_1") (pintype "passive"))
      (node (ref "C9") (pin "1") (pinfunction "1_1") (pintype "passive"))
      (node (ref "D7") (pin "2") (pinfunction "K_2") (pintype "passive"))
      (node (ref "FB2") (pin "1") (pinfunction "1_1") (pintype "passive"))
      (node (ref "LCD1") (pin "1") (pinfunction "GND_1") (pintype "passive"))
      (node (ref "LCD1") (pin "16") (pinfunction "K_16") (pintype "passive"))
      (node (ref "P1") (pin "5") (pinfunction "5_5") (pintype "passive"))
      (node (ref "P2") (pin "10") (pinfunction "10_10") (pintype "passive"))
      (node (ref "P3") (pin "11") (pinfunction "11_11") (pintype "passive"))
      (node (ref "P4") (pin "3") (pinfunction "3_3") (pintype "passive"))
      (node (ref "Q1") (pin "2") (pinfunction "E_2") (pintype "passive"))
      (node (ref "Q2") (pin "2") (pinfunction "E_2") (pintype "passive"))
      (node (ref "Q3") (pin "2") (pinfunction "E_2") (pintype "passive"))
      (node (ref "Q4") (pin "2") (pinfunction "E_2") (pintype "passive"))
      (node (ref "R1") (pin "1") (pinfunction "1_1") (pintype "passive"))
      (node (ref "R12") (pin "1") (pinfunction "1_1") (pintype "passive"))
      (node (ref "R13") (pin "1") (pinfunction "1_1") (pintype "passive"))
      (node (ref "R14") (pin "1") (pinfunction "1_1") (pintype "passive"))
      (node (ref "R2") (pin "1") (pinfunction "1_1") (pintype "passive"))
      (node (ref "R21") (pin "1") (pinfunction "1_1") (pintype "passive"))
      (node (ref "R22") (pin "1") (pinfunction "1_1") (pintype "passive"))
      (node (ref "R26") (pin "1") (pinfunction "1_1") (pintype "passive"))
      (node (ref "R27") (pin "1") (pinfunction "1_1") (pintype "passive"))
      (node (ref "R28") (pin "1") (pinfunction "1_1") (pintype "passive"))
      (node (ref "R29") (pin "1") (pinfunction "1_1") (pintype "passive"))
      (node (ref "R3") (pin "1") (pinfunction "1_1") (pintype "passive"))
      (node (ref "R31") (pin "2") (pinfunction "BOT_2") (pintype "passive"))
      (node (ref "R4") (pin "1") (pinfunction "1_1") (pintype "passive"))
      (node (ref "R5") (pin "1") (pinfunction "1_1") (pintype "passive"))
      (node (ref "R6") (pin "1") (pinfunction "TOP_1") (pintype "passive"))
      (node (ref "S1") (pin "1") (pinfunction "1_1") (pintype "passive"))
      (node (ref "SD1") (pin "10") (pinfunction "BODY_10") (pintype "passive"))
      (node (ref "SD1") (pin "11") (pinfunction "BODY_11") (pintype "passive"))
      (node (ref "SD1") (pin "12") (pinfunction "BODY_12") (pintype "passive"))
      (node (ref "SD1") (pin "13") (pinfunction "BODY_13") (pintype "passive"))
      (node (ref "SD1") (pin "6") (pinfunction "VSS_6") (pintype "passive"))
      (node (ref "U1") (pin "18") (pinfunction "VSS_4_18") (pintype "power_in"))
      (node (ref "U1") (pin "31") (pinfunction "VSS_1_31") (pintype "power_in"))
      (node (ref "U1") (pin "47") (pinfunction "VSS_2_47") (pintype "power_in"))
      (node (ref "U1") (pin "63") (pinfunction "VSS_3_63") (pintype "power_in"))
      (node (ref "U3") (pin "18") (pinfunction "GND_18") (pintype "passive"))
      (node (ref "U3") (pin "21") (pinfunction "GND_21") (pintype "passive"))
      (node (ref "U3") (pin "25") (pinfunction "AGND_25") (pintype "passive"))
      (node (ref "U3") (pin "26") (pinfunction "TEST_26") (pintype "passive"))
      (node (ref "U3") (pin "7") (pinfunction "GND_7") (pintype "passive"))
      (node (ref "U5") (pin "1") (pinfunction "A0_1") (pintype "passive"))
      (node (ref "U5") (pin "2") (pinfunction "A1_2") (pintype "passive"))
      (node (ref "U5") (pin "3") (pinfunction "NC_3") (pintype "passive"))
      (node (ref "U5") (pin "4") (pinfunction "GND_4") (pintype "passive"))
      (node (ref "U5") (pin "7") (pinfunction "WP_7") (pintype "passive"))
      (node (ref "U6") (pin "1") (pinfunction "GND_1") (pintype "passive"))
      (node (ref "USB1") (pin "5") (pinfunction "GND_5") (pintype "passive"))
    )
    (net (code "52") (name "GNDA") (class "Default")
      (node (ref "C7") (pin "1") (pinfunction "1_1") (pintype "passive"))
      (node (ref "C8") (pin "2") (pinfunction "2_2") (pintype "passive"))
      (node (ref "FB2") (pin "2") (pinfunction "2_2") (pintype "passive"))
      (node (ref "U1") (pin "12") (pinfunction "VSSA_12") (pintype "power_in"))
      (node (ref "U4") (pin "3") (pinfunction "GND_3") (pintype "passive"))
    )
    (net (code "53") (name "Net-(D1-A)") (class "Default")
      (node (ref "D1") (pin "1") (pinfunction "A_1") (pintype "passive"))
      (node (ref "R8") (pin "1") (pinfunction "1_1") (pintype "passive"))
    )
    (net (code "54") (name "Net-(D1-K)") (class "Default")
      (node (ref "D1") (pin "2") (pinfunction "K_2") (pintype "passive"))
      (node (ref "Q1") (pin "3") (pinfunction "C_3") (pintype "passive"))
    )
    (net (code "55") (name "Net-(D2-A)") (class "Default")
      (node (ref "D2") (pin "1") (pinfunction "A_1") (pintype "passive"))
      (node (ref "R9") (pin "1") (pinfunction "1_1") (pintype "passive"))
    )
    (net (code "56") (name "Net-(D2-K)") (class "Default")
      (node (ref "D2") (pin "2") (pinfunction "K_2") (pintype "passive"))
      (node (ref "Q2") (pin "3") (pinfunction "C_3") (pintype "passive"))
    )
    (net (code "57") (name "Net-(D3-A)") (class "Default")
      (node (ref "D3") (pin "1") (pinfunction "A_1") (pintype "passive"))
      (node (ref "R15") (pin "1") (pinfunction "1_1") (pintype "passive"))
    )
    (net (code "58") (name "Net-(D3-K)") (class "Default")
      (node (ref "D3") (pin "2") (pinfunction "K_2") (pintype "passive"))
      (node (ref "Q3") (pin "3") (pinfunction "C_3") (pintype "passive"))
    )
    (net (code "59") (name "Net-(D4-A)") (class "Default")
      (node (ref "D4") (pin "1") (pinfunction "A_1") (pintype "passive"))
      (node (ref "R16") (pin "1") (pinfunction "1_1") (pintype "passive"))
    )
    (net (code "60") (name "Net-(D4-K)") (class "Default")
      (node (ref "D4") (pin "2") (pinfunction "K_2") (pintype "passive"))
      (node (ref "Q4") (pin "3") (pinfunction "C_3") (pintype "passive"))
    )
    (net (code "61") (name "Net-(D5-A)") (class "Default")
      (node (ref "D5") (pin "1") (pinfunction "A_1") (pintype "passive"))
      (node (ref "R18") (pin "1") (pinfunction "1_1") (pintype "passive"))
    )
    (net (code "62") (name "Net-(D5-K)") (class "Default")
      (node (ref "D5") (pin "2") (pinfunction "K_2") (pintype "passive"))
      (node (ref "U3") (pin "23") (pinfunction "CBUS0_23") (pintype "passive"))
    )
    (net (code "63") (name "Net-(D6-A)") (class "Default")
      (node (ref "D6") (pin "1") (pinfunction "A_1") (pintype "passive"))
      (node (ref "R19") (pin "1") (pinfunction "1_1") (pintype "passive"))
    )
    (net (code "64") (name "Net-(D6-K)") (class "Default")
      (node (ref "D6") (pin "2") (pinfunction "K_2") (pintype "passive"))
      (node (ref "U3") (pin "22") (pinfunction "CBUS1_22") (pintype "passive"))
    )
    (net (code "65") (name "Net-(D7-A)") (class "Default")
      (node (ref "D7") (pin "1") (pinfunction "A_1") (pintype "passive"))
      (node (ref "R30") (pin "1") (pinfunction "1_1") (pintype "passive"))
    )
    (net (code "66") (name "Net-(LCD1-D0)") (class "Default")
      (node (ref "LCD1") (pin "7") (pinfunction "D0_7") (pintype "passive"))
      (node (ref "R2") (pin "2") (pinfunction "2_2") (pintype "passive"))
    )
    (net (code "67") (name "Net-(LCD1-D1)") (class "Default")
      (node (ref "LCD1") (pin "8") (pinfunction "D1_8") (pintype "passive"))
      (node (ref "R3") (pin "2") (pinfunction "2_2") (pintype "passive"))
    )
    (net (code "68") (name "Net-(LCD1-D2)") (class "Default")
      (node (ref "LCD1") (pin "9") (pinfunction "D2_9") (pintype "passive"))
      (node (ref "R4") (pin "2") (pinfunction "2_2") (pintype "passive"))
    )
    (net (code "69") (name "Net-(LCD1-D3)") (class "Default")
      (node (ref "LCD1") (pin "10") (pinfunction "D3_10") (pintype "passive"))
      (node (ref "R1") (pin "2") (pinfunction "2_2") (pintype "passive"))
    )
    (net (code "70") (name "Net-(LCD1-VO)") (class "Default")
      (node (ref "LCD1") (pin "3") (pinfunction "VO_3") (pintype "passive"))
      (node (ref "R6") (pin "3") (pinfunction "TAP_3") (pintype "passive"))
    )
    (net (code "71") (name "Net-(Q1-B)") (class "Default")
      (node (ref "Q1") (pin "1") (pinfunction "B_1") (pintype "passive"))
      (node (ref "R10") (pin "2") (pinfunction "2_2") (pintype "passive"))
      (node (ref "R13") (pin "2") (pinfunction "2_2") (pintype "passive"))
    )
    (net (code "72") (name "Net-(Q2-B)") (class "Default")
      (node (ref "Q2") (pin "1") (pinfunction "B_1") (pintype "passive"))
      (node (ref "R11") (pin "2") (pinfunction "2_2") (pintype "passive"))
      (node (ref "R14") (pin "2") (pinfunction "2_2") (pintype "passive"))
    )
    (net (code "73") (name "Net-(Q3-B)") (class "Default")
      (node (ref "Q3") (pin "1") (pinfunction "B_1") (pintype "passive"))
      (node (ref "R17") (pin "2") (pinfunction "2_2") (pintype "passive"))
      (node (ref "R21") (pin "2") (pinfunction "2_2") (pintype "passive"))
    )
    (net (code "74") (name "Net-(Q4-B)") (class "Default")
      (node (ref "Q4") (pin "1") (pinfunction "B_1") (pintype "passive"))
      (node (ref "R20") (pin "2") (pinfunction "2_2") (pintype "passive"))
      (node (ref "R22") (pin "2") (pinfunction "2_2") (pintype "passive"))
    )
    (net (code "75") (name "Net-(U1-PB2{slash}BOOT1)") (class "Default")
      (node (ref "R5") (pin "2") (pinfunction "2_2") (pintype "passive"))
      (node (ref "U1") (pin "28") (pinfunction "PB2/BOOT1_28") (pintype "bidirectional"))
    )
    (net (code "76") (name "Net-(U1-PC14-OSC32_IN)") (class "Default")
      (node (ref "C9") (pin "2") (pinfunction "2_2") (pintype "passive"))
      (node (ref "U1") (pin "3") (pinfunction "PC14-OSC32_IN_3") (pintype "bidirectional"))
      (node (ref "Y2") (pin "1") (pinfunction "OSC1_1") (pintype "passive"))
    )
    (net (code "77") (name "Net-(U1-PC15-OSC32_OUT)") (class "Default")
      (node (ref "C11") (pin "2") (pinfunction "2_2") (pintype "passive"))
      (node (ref "U1") (pin "4") (pinfunction "PC15-OSC32_OUT_4") (pintype "bidirectional"))
      (node (ref "Y2") (pin "2") (pinfunction "OSC2_2") (pintype "passive"))
    )
    (net (code "78") (name "Net-(U3-USBDM)") (class "Default")
      (node (ref "U3") (pin "16") (pinfunction "USBDM_16") (pintype "passive"))
      (node (ref "USB1") (pin "2") (pinfunction "D-_2") (pintype "passive"))
    )
    (net (code "79") (name "Net-(U3-USBDP)") (class "Default")
      (node (ref "U3") (pin "15") (pinfunction "USBDP_15") (pintype "passive"))
      (node (ref "USB1") (pin "3") (pinfunction "D+_3") (pintype "passive"))
    )
    (net (code "80") (name "Net-(U6-OUT)") (class "Default")
      (node (ref "C21") (pin "2") (pinfunction "2_2") (pintype "passive"))
      (node (ref "C23") (pin "1") (pinfunction "1_1") (pintype "passive"))
      (node (ref "FB4") (pin "1") (pinfunction "1_1") (pintype "passive"))
      (node (ref "U6") (pin "2") (pinfunction "OUT_2") (pintype "passive"))
    )
    (net (code "81") (name "Net-(USB1-VCC)") (class "Default")
      (node (ref "FB3") (pin "1") (pinfunction "1_1") (pintype "passive"))
      (node (ref "USB1") (pin "1") (pinfunction "VCC_1") (pintype "passive"))
    )
    (net (code "82") (name "VCCIO") (class "Default")
      (node (ref "C13") (pin "2") (pinfunction "2_2") (pintype "passive"))
      (node (ref "R18") (pin "2") (pinfunction "2_2") (pintype "passive"))
      (node (ref "R19") (pin "2") (pinfunction "2_2") (pintype "passive"))
      (node (ref "U3") (pin "17") (pinfunction "3V3OUT_17") (pintype "passive"))
      (node (ref "U3") (pin "4") (pinfunction "VCCIO_4") (pintype "passive"))
    )
    (net (code "83") (name "unconnected-(SD1-DAT1-Pad8)") (class "Default")
      (node (ref "SD1") (pin "8") (pinfunction "DAT1_8") (pintype "passive+no_connect"))
    )
    (net (code "84") (name "unconnected-(SD1-DAT2-Pad1)") (class "Default")
      (node (ref "SD1") (pin "1") (pinfunction "DAT2_1") (pintype "passive+no_connect"))
    )
    (net (code "85") (name "unconnected-(SD1-RSV-Pad9)") (class "Default")
      (node (ref "SD1") (pin "9") (pinfunction "RSV_9") (pintype "passive+no_connect"))
    )
    (net (code "86") (name "unconnected-(U1-PB0-Pad26)") (class "Default")
      (node (ref "U1") (pin "26") (pinfunction "PB0_26") (pintype "bidirectional+no_connect"))
    )
    (net (code "87") (name "unconnected-(U1-PB8-Pad61)") (class "Default")
      (node (ref "U1") (pin "61") (pinfunction "PB8_61") (pintype "bidirectional+no_connect"))
    )
    (net (code "88") (name "unconnected-(U1-PB9-Pad62)") (class "Default")
      (node (ref "U1") (pin "62") (pinfunction "PB9_62") (pintype "bidirectional+no_connect"))
    )
    (net (code "89") (name "unconnected-(U1-PB10-Pad29)") (class "Default")
      (node (ref "U1") (pin "29") (pinfunction "PB10_29") (pintype "bidirectional+no_connect"))
    )
    (net (code "90") (name "unconnected-(U3-CBUS2-Pad13)") (class "Default")
      (node (ref "U3") (pin "13") (pinfunction "CBUS2_13") (pintype "passive+no_connect"))
    )
    (net (code "91") (name "unconnected-(U3-CBUS3-Pad14)") (class "Default")
      (node (ref "U3") (pin "14") (pinfunction "CBUS3_14") (pintype "passive+no_connect"))
    )
    (net (code "92") (name "unconnected-(U3-CBUS4-Pad12)") (class "Default")
      (node (ref "U3") (pin "12") (pinfunction "CBUS4_12") (pintype "passive+no_connect"))
    )
    (net (code "93") (name "unconnected-(U3-CTS#-Pad11)") (class "Default")
      (node (ref "U3") (pin "11") (pinfunction "CTS#_11") (pintype "passive+no_connect"))
    )
    (net (code "94") (name "unconnected-(U3-DCD#-Pad10)") (class "Default")
      (node (ref "U3") (pin "10") (pinfunction "DCD#_10") (pintype "passive+no_connect"))
    )
    (net (code "95") (name "unconnected-(U3-DSR#-Pad9)") (class "Default")
      (node (ref "U3") (pin "9") (pinfunction "DSR#_9") (pintype "passive+no_connect"))
    )
    (net (code "96") (name "unconnected-(U3-DTR#-Pad2)") (class "Default")
      (node (ref "U3") (pin "2") (pinfunction "DTR#_2") (pintype "passive+no_connect"))
    )
    (net (code "97") (name "unconnected-(U3-NC-Pad8)") (class "Default")
      (node (ref "U3") (pin "8") (pinfunction "NC_8") (pintype "passive+no_connect"))
    )
    (net (code "98") (name "unconnected-(U3-NC-Pad24)") (class "Default")
      (node (ref "U3") (pin "24") (pinfunction "NC_24") (pintype "passive+no_connect"))
    )
    (net (code "99") (name "unconnected-(U3-OCSI-Pad27)") (class "Default")
      (node (ref "U3") (pin "27") (pinfunction "OCSI_27") (pintype "passive+no_connect"))
    )
    (net (code "100") (name "unconnected-(U3-OCSO-Pad28)") (class "Default")
      (node (ref "U3") (pin "28") (pinfunction "OCSO_28") (pintype "passive+no_connect"))
    )
    (net (code "101") (name "unconnected-(U3-RESET#-Pad19)") (class "Default")
      (node (ref "U3") (pin "19") (pinfunction "RESET#_19") (pintype "passive+no_connect"))
    )
    (net (code "102") (name "unconnected-(U3-RI#-Pad6)") (class "Default")
      (node (ref "U3") (pin "6") (pinfunction "RI#_6") (pintype "passive+no_connect"))
    )
    (net (code "103") (name "unconnected-(U3-RTS#-Pad3)") (class "Default")
      (node (ref "U3") (pin "3") (pinfunction "RTS#_3") (pintype "passive+no_connect"))
    )
    (net (code "104") (name "unconnected-(USB1-NC-Pad4)") (class "Default")
      (node (ref "USB1") (pin "4") (pinfunction "NC_4") (pintype "passive+no_connect"))
    )
  )
)
